# cape.net
KiCad netlist of a schematic drawn in Altium Designer
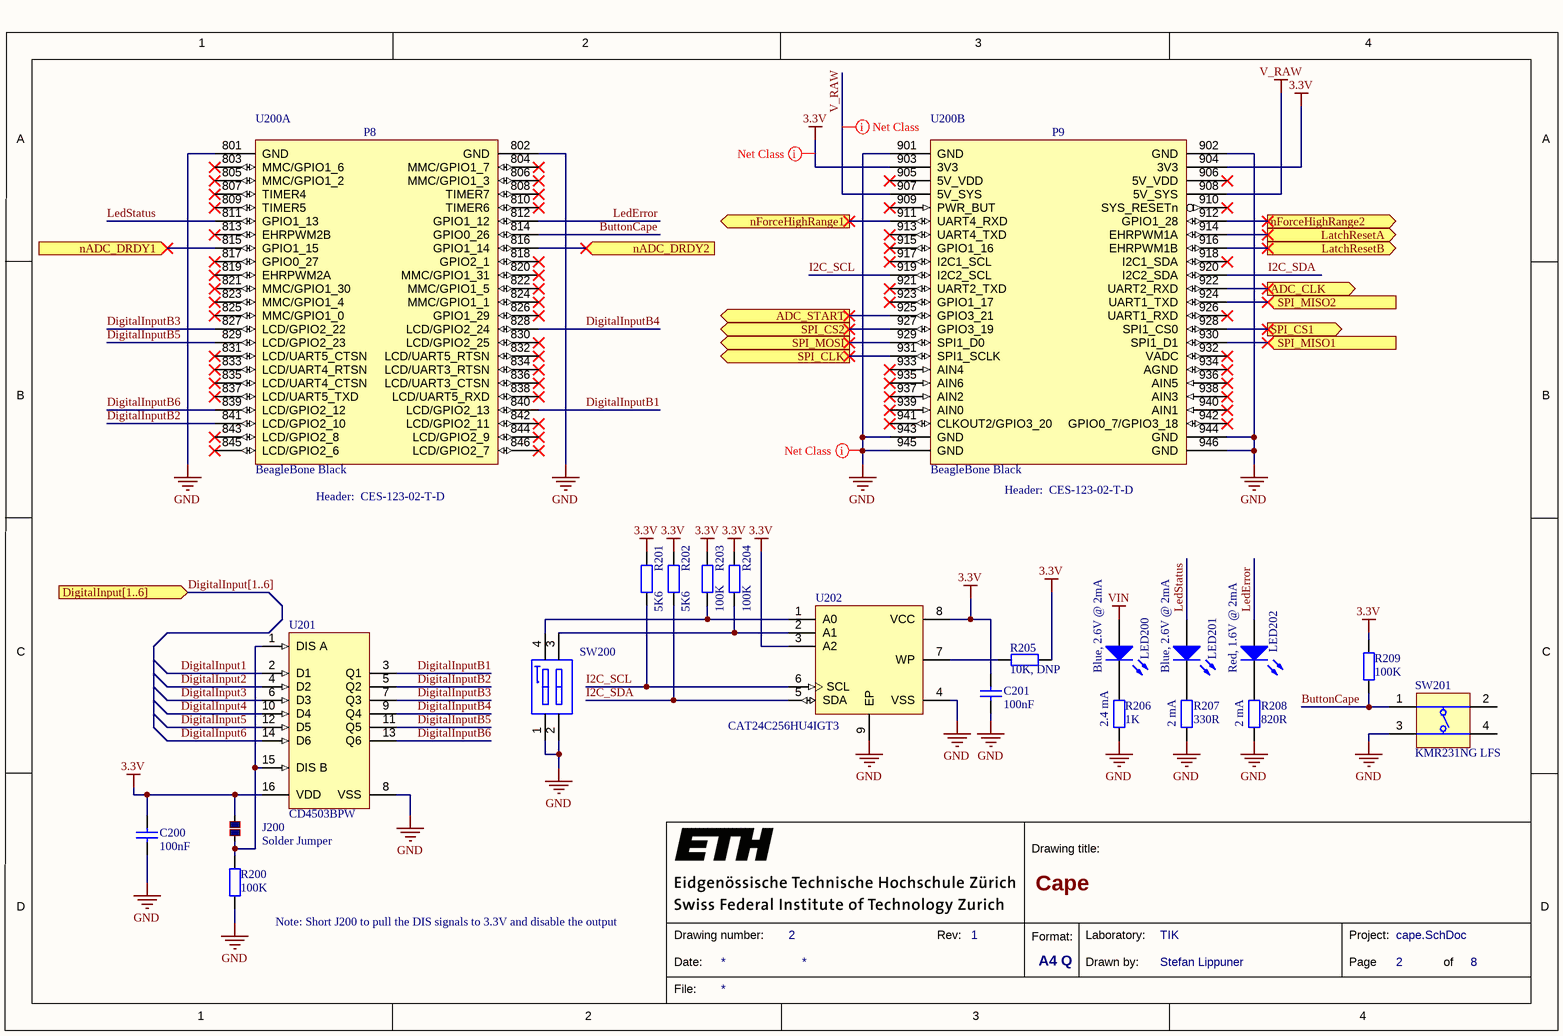
[diagram p0: cape.SchDoc]

(export (version "E")
  (design (tool "Eeschema 10.0.6"))
  (components
    (comp (ref "C200")
      (value "100nF")
      (footprint "CAPC0402(1005)60_L")
      (description "CAP 100nF 16V -20% to +80% 0402 (1005 Metric) Thickness 0.6mm SMD")
      (fields (field (name "TOLERANCE") "-20% to +80%"))
      (libsource (lib "Altium Content Vault") (part "CMP-1034-02071-1"))
    )
    (comp (ref "C201")
      (value "100nF")
      (footprint "CAPC0402(1005)60_L")
      (description "CAP 100nF 16V -20% to +80% 0402 (1005 Metric) Thickness 0.6mm SMD")
      (fields (field (name "TOLERANCE") "-20% to +80%"))
      (libsource (lib "Altium Content Vault") (part "CMP-1034-02071-1"))
    )
    (comp (ref "J200")
      (value "Solder Jumper")
      (footprint "Small Solder Jumper")
      (libsource (lib "ETHZ Vault") (part "CMP-00005-1"))
    )
    (comp (ref "LED200")
      (value "Blue, 2.6V @ 2mA")
      (footprint "0603_A")
      (description "SMD mono-color Chip LED, WL-SMCW, Blue")
      (fields (field (name "PARTNUMBER") "150060BS75000") (field (name "MANUFACTURER") "Wuerth Elektronik"))
      (libsource (lib "Altium Content Vault") (part "CMP-1426-00003-1"))
    )
    (comp (ref "LED201")
      (value "Blue, 2.6V @ 2mA")
      (footprint "0603_A")
      (description "SMD mono-color Chip LED, WL-SMCW, Blue")
      (fields (field (name "PARTNUMBER") "150060BS75000") (field (name "MANUFACTURER") "Wuerth Elektronik"))
      (libsource (lib "Altium Content Vault") (part "CMP-1426-00003-1"))
    )
    (comp (ref "LED202")
      (value "Red, 1.6V @ 2mA")
      (footprint "0603_A")
      (description "SMD mono-color Chip LED, WL-SMCW, Red")
      (fields (field (name "MANUFACTURER") "Wuerth Elektronik") (field (name "PARTNUMBER") "150060RS75000"))
      (libsource (lib "Altium Content Vault") (part "WE-LED_K1A2-2"))
    )
    (comp (ref "P8")
      (value "CES-123-02-T-D (BOM)")
      (libsource (lib "CES-123-02-T-D") (part "CES-123-02-T-D (BOM)"))
    )
    (comp (ref "P9")
      (value "CES-123-02-T-D (BOM)")
      (libsource (lib "CES-123-02-T-D") (part "CES-123-02-T-D (BOM)"))
    )
    (comp (ref "R200")
      (value "100K")
      (footprint "RESC0402(1005)_L")
      (description "100K 0.063W 1% 0402 (1005 Metric)  SMD")
      (fields (field (name "TOLERANCE") "1 %") (field (name "POWER") "0.063 W"))
      (libsource (lib "Altium Content Vault") (part "CMP-1011-00736"))
    )
    (comp (ref "R201")
      (value "5K6")
      (footprint "RESC0402(1005)_L")
      (description "5K6 0.063W 5% 0402 (1005 Metric)  SMD")
      (fields (field (name "TOLERANCE") "5 %") (field (name "POWER") "0.063 W"))
      (libsource (lib "Altium Content Vault") (part "CMP-1011-00092-1"))
    )
    (comp (ref "R202")
      (value "5K6")
      (footprint "RESC0402(1005)_L")
      (description "5K6 0.063W 5% 0402 (1005 Metric)  SMD")
      (fields (field (name "TOLERANCE") "5 %") (field (name "POWER") "0.063 W"))
      (libsource (lib "Altium Content Vault") (part "CMP-1011-00092-1"))
    )
    (comp (ref "R203")
      (value "100K")
      (footprint "RESC0402(1005)_L")
      (description "100K 0.063W 1% 0402 (1005 Metric)  SMD")
      (fields (field (name "POWER") "0.063 W") (field (name "TOLERANCE") "1 %"))
      (libsource (lib "Altium Content Vault") (part "CMP-1011-00736"))
    )
    (comp (ref "R204")
      (value "100K")
      (footprint "RESC0402(1005)_L")
      (description "100K 0.063W 1% 0402 (1005 Metric)  SMD")
      (fields (field (name "POWER") "0.063 W") (field (name "TOLERANCE") "1 %"))
      (libsource (lib "Altium Content Vault") (part "CMP-1011-00736"))
    )
    (comp (ref "R205")
      (value "10K, DNP")
      (footprint "RESC0402(1005)_L")
      (description "10K 0.063W 1% 0402 (1005 Metric)  SMD")
      (fields (field (name "TOLERANCE") "1 %") (field (name "POWER") "0.063 W"))
      (libsource (lib "Altium Content Vault") (part "CMP-1011-00623-1"))
    )
    (comp (ref "R206")
      (value "1K")
      (footprint "RESC0402(1005)_L")
      (description "1K 0.063W 1% 0402 (1005 Metric)  SMD")
      (fields (field (name "TOLERANCE") "1 %") (field (name "POWER") "0.063 W"))
      (libsource (lib "Altium Content Vault") (part "RES"))
    )
    (comp (ref "R207")
      (value "330R")
      (footprint "RESC0402(1005)_L")
      (description "330R 0.063W 5% 0402 (1005 Metric)  SMD")
      (fields (field (name "TOLERANCE") "5 %") (field (name "POWER") "0.063 W"))
      (libsource (lib "Altium Content Vault") (part "CMP-1011-00062-1"))
    )
    (comp (ref "R208")
      (value "820R")
      (footprint "RESC0402(1005)_L")
      (description "820R 0.063W 5% 0402 (1005 Metric)  SMD")
      (fields (field (name "TOLERANCE") "5 %") (field (name "POWER") "0.063 W"))
      (libsource (lib "Altium Content Vault") (part "CMP-1011-00072-1"))
    )
    (comp (ref "R209")
      (value "100K")
      (footprint "RESC0402(1005)_L")
      (description "100K 0.063W 1% 0402 (1005 Metric)  SMD")
      (fields (field (name "TOLERANCE") "1 %") (field (name "POWER") "0.063 W"))
      (libsource (lib "Altium Content Vault") (part "CMP-1011-00736"))
    )
    (comp (ref "SW200")
      (value "218-2LPST")
      (footprint "416131160802")
      (description "Switch DIP ON OFF SPST 2 Recessed Slide 0.025A 24VDC Gull Wing 1.27mm SMD")
      (fields (field (name "MANUFACTURER") "CTS Electrocomponents"))
      (libsource (lib "ETHZ Vault") (part "WE-DIP-SW-4"))
    )
    (comp (ref "SW201")
      (value "KMR231NG LFS")
      (footprint "KRM 2 Series")
      (description "SWITCH TACTILE SPST-NO 0.05A 32V")
      (fields (field (name "MANUFACTURER") "C&K Components"))
      (libsource (lib "ETHZ Vault") (part "SW-Push Button"))
    )
    (comp (ref "U200") (value "BeagleBone Black") (libsource (lib "ETHZ Vault") (part "CMP-00111-2")))
    (comp (ref "U201")
      (value "CD4503BPW")
      (footprint "PW0016A_L")
      (description "CMOS Hex Non-Inverting Buffer with 3-State Outputs, PW0016A, TUBE")
      (fields
        (field (name "MANUFACTURER") "Texas Instruments")
        (field (name "GENERIC PART NUMBER") "CD4503B")
      )
      (libsource (lib "Altium Content Vault") (part "TI-CD4503B-16"))
    )
    (comp (ref "U202")
      (value "CAT24C256HU4IGT3")
      (footprint "UDFN-MU8")
      (description "IC EEPROM 256KBIT 400KHZ 8UDFN")
      (fields (field (name "MANUFACTURER") "ON Semiconductor"))
      (libsource (lib "ETHZ Vault") (part "CAT24C256"))
    )
  )
  (nets
    (net (code "1") (name "/ADC_CLK") (class "Default")
      (node (ref "U200") (pin "922") (pinfunction "UART2_RXD_922") (pintype "bidirectional+no_connect"))
    )
    (net (code "2") (name "/ADC_START") (class "Default")
      (node (ref "U200") (pin "925") (pinfunction "GPIO3_21_925") (pintype "bidirectional+no_connect"))
    )
    (net (code "3") (name "/ButtonCape") (class "Default")
      (node (ref "R209") (pin "1") (pinfunction "1_1") (pintype "passive"))
      (node (ref "SW201") (pin "1") (pinfunction "T1_1") (pintype "passive"))
      (node (ref "U200") (pin "814") (pinfunction "GPIO0_26_814") (pintype "bidirectional"))
    )
    (net (code "4") (name "/DigitalInput1") (class "Default")
      (node (ref "U201") (pin "2") (pinfunction "D1_2") (pintype "input"))
    )
    (net (code "5") (name "/DigitalInput2") (class "Default")
      (node (ref "U201") (pin "4") (pinfunction "D2_4") (pintype "input"))
    )
    (net (code "6") (name "/DigitalInput3") (class "Default")
      (node (ref "U201") (pin "6") (pinfunction "D3_6") (pintype "input"))
    )
    (net (code "7") (name "/DigitalInput4") (class "Default")
      (node (ref "U201") (pin "10") (pinfunction "D4_10") (pintype "input"))
    )
    (net (code "8") (name "/DigitalInput5") (class "Default")
      (node (ref "U201") (pin "12") (pinfunction "D5_12") (pintype "input"))
    )
    (net (code "9") (name "/DigitalInput6") (class "Default")
      (node (ref "U201") (pin "14") (pinfunction "D6_14") (pintype "input"))
    )
    (net (code "10") (name "/DigitalInputB1") (class "Default")
      (node (ref "U200") (pin "840") (pinfunction "LCD/GPIO2_13_840") (pintype "bidirectional"))
      (node (ref "U201") (pin "3") (pinfunction "Q1_3") (pintype "tri_state"))
    )
    (net (code "11") (name "/DigitalInputB2") (class "Default")
      (node (ref "U200") (pin "841") (pinfunction "LCD/GPIO2_10_841") (pintype "bidirectional"))
      (node (ref "U201") (pin "5") (pinfunction "Q2_5") (pintype "tri_state"))
    )
    (net (code "12") (name "/DigitalInputB3") (class "Default")
      (node (ref "U200") (pin "827") (pinfunction "LCD/GPIO2_22_827") (pintype "bidirectional"))
      (node (ref "U201") (pin "7") (pinfunction "Q3_7") (pintype "tri_state"))
    )
    (net (code "13") (name "/DigitalInputB4") (class "Default")
      (node (ref "U200") (pin "828") (pinfunction "LCD/GPIO2_24_828") (pintype "bidirectional"))
      (node (ref "U201") (pin "9") (pinfunction "Q4_9") (pintype "tri_state"))
    )
    (net (code "14") (name "/DigitalInputB5") (class "Default")
      (node (ref "U200") (pin "829") (pinfunction "LCD/GPIO2_23_829") (pintype "bidirectional"))
      (node (ref "U201") (pin "11") (pinfunction "Q5_11") (pintype "tri_state"))
    )
    (net (code "15") (name "/DigitalInputB6") (class "Default")
      (node (ref "U200") (pin "839") (pinfunction "LCD/GPIO2_12_839") (pintype "bidirectional"))
      (node (ref "U201") (pin "13") (pinfunction "Q6_13") (pintype "tri_state"))
    )
    (net (code "17") (name "/I2C_SCL") (class "Default")
      (node (ref "R201") (pin "1") (pinfunction "1_1") (pintype "passive"))
      (node (ref "U200") (pin "919") (pinfunction "I2C2_SCL_919") (pintype "bidirectional"))
      (node (ref "U202") (pin "6") (pinfunction "SCL_6") (pintype "input"))
    )
    (net (code "18") (name "/I2C_SDA") (class "Default")
      (node (ref "R202") (pin "1") (pinfunction "1_1") (pintype "passive"))
      (node (ref "U200") (pin "920") (pinfunction "I2C2_SDA_920") (pintype "bidirectional"))
      (node (ref "U202") (pin "5") (pinfunction "SDA_5") (pintype "bidirectional"))
    )
    (net (code "19") (name "/LatchResetA") (class "Default")
      (node (ref "U200") (pin "914") (pinfunction "EHRPWM1A_914") (pintype "bidirectional+no_connect"))
    )
    (net (code "20") (name "/LatchResetB") (class "Default")
      (node (ref "U200") (pin "916") (pinfunction "EHRPWM1B_916") (pintype "bidirectional+no_connect"))
    )
    (net (code "21") (name "/LedError") (class "Default")
      (node (ref "LED202") (pin "2") (pinfunction "A_2") (pintype "passive"))
      (node (ref "U200") (pin "812") (pinfunction "GPIO1_12_812") (pintype "bidirectional"))
    )
    (net (code "22") (name "/LedStatus") (class "Default")
      (node (ref "LED201") (pin "2") (pinfunction "A_2") (pintype "passive"))
      (node (ref "U200") (pin "811") (pinfunction "GPIO1_13_811") (pintype "bidirectional"))
    )
    (net (code "23") (name "/SPI_CLK") (class "Default")
      (node (ref "U200") (pin "931") (pinfunction "SPI1_SCLK_931") (pintype "bidirectional+no_connect"))
    )
    (net (code "24") (name "/SPI_CS1") (class "Default")
      (node (ref "U200") (pin "928") (pinfunction "SPI1_CS0_928") (pintype "bidirectional+no_connect"))
    )
    (net (code "25") (name "/SPI_CS2") (class "Default")
      (node (ref "U200") (pin "927") (pinfunction "GPIO3_19_927") (pintype "bidirectional+no_connect"))
    )
    (net (code "26") (name "/SPI_MISO1") (class "Default")
      (node (ref "U200") (pin "930") (pinfunction "SPI1_D1_930") (pintype "bidirectional+no_connect"))
    )
    (net (code "27") (name "/SPI_MISO2") (class "Default")
      (node (ref "U200") (pin "924") (pinfunction "UART1_TXD_924") (pintype "bidirectional+no_connect"))
    )
    (net (code "28") (name "/SPI_MOSI") (class "Default")
      (node (ref "U200") (pin "929") (pinfunction "SPI1_D0_929") (pintype "bidirectional+no_connect"))
    )
    (net (code "29") (name "/nADC_DRDY1") (class "Default")
      (node (ref "U200") (pin "815") (pinfunction "GPIO1_15_815") (pintype "bidirectional+no_connect"))
    )
    (net (code "30") (name "/nADC_DRDY2") (class "Default")
      (node (ref "U200") (pin "816") (pinfunction "GPIO1_14_816") (pintype "bidirectional+no_connect"))
    )
    (net (code "31") (name "/nForceHighRange1") (class "Default")
      (node (ref "U200") (pin "911") (pinfunction "UART4_RXD_911") (pintype "bidirectional+no_connect"))
    )
    (net (code "32") (name "/nForceHighRange2") (class "Default")
      (node (ref "U200") (pin "912") (pinfunction "GPIO1_28_912") (pintype "bidirectional+no_connect"))
    )
    (net (code "33") (name "3.3V") (class "Default")
      (node (ref "C200") (pin "2") (pinfunction "2_2") (pintype "passive"))
      (node (ref "C201") (pin "2") (pinfunction "2_2") (pintype "passive"))
      (node (ref "J200") (pin "2") (pintype "passive"))
      (node (ref "R201") (pin "2") (pinfunction "2_2") (pintype "passive"))
      (node (ref "R202") (pin "2") (pinfunction "2_2") (pintype "passive"))
      (node (ref "R203") (pin "2") (pinfunction "2_2") (pintype "passive"))
      (node (ref "R204") (pin "2") (pinfunction "2_2") (pintype "passive"))
      (node (ref "R205") (pin "2") (pinfunction "2_2") (pintype "passive"))
      (node (ref "R209") (pin "2") (pinfunction "2_2") (pintype "passive"))
      (node (ref "U200") (pin "903") (pinfunction "3V3_903") (pintype "power_in"))
      (node (ref "U200") (pin "904") (pinfunction "3V3_904") (pintype "power_in"))
      (node (ref "U201") (pin "16") (pinfunction "VDD_16") (pintype "power_in"))
      (node (ref "U202") (pin "3") (pinfunction "A2_3") (pintype "passive"))
      (node (ref "U202") (pin "8") (pinfunction "VCC_8") (pintype "power_in"))
    )
    (net (code "34") (name "GND") (class "Default")
      (node (ref "C200") (pin "1") (pinfunction "1_1") (pintype "passive"))
      (node (ref "C201") (pin "1") (pinfunction "1_1") (pintype "passive"))
      (node (ref "R200") (pin "1") (pinfunction "1_1") (pintype "passive"))
      (node (ref "R206") (pin "1") (pinfunction "1_1") (pintype "passive"))
      (node (ref "R207") (pin "1") (pinfunction "1_1") (pintype "passive"))
      (node (ref "R208") (pin "1") (pinfunction "1_1") (pintype "passive"))
      (node (ref "SW200") (pin "1") (pinfunction "1_1") (pintype "passive"))
      (node (ref "SW200") (pin "2") (pinfunction "2_2") (pintype "passive"))
      (node (ref "SW201") (pin "3") (pinfunction "T3_3") (pintype "passive"))
      (node (ref "U200") (pin "801") (pinfunction "GND_801") (pintype "power_in"))
      (node (ref "U200") (pin "802") (pinfunction "GND_802") (pintype "power_in"))
      (node (ref "U200") (pin "901") (pinfunction "GND_901") (pintype "passive"))
      (node (ref "U200") (pin "902") (pinfunction "GND_902") (pintype "passive"))
      (node (ref "U200") (pin "943") (pinfunction "GND_943") (pintype "power_in"))
      (node (ref "U200") (pin "944") (pinfunction "GND_944") (pintype "power_in"))
      (node (ref "U200") (pin "945") (pinfunction "GND_945") (pintype "power_in"))
      (node (ref "U200") (pin "946") (pinfunction "GND_946") (pintype "power_in"))
      (node (ref "U201") (pin "8") (pinfunction "VSS_8") (pintype "power_in"))
      (node (ref "U202") (pin "4") (pinfunction "VSS_4") (pintype "power_in"))
      (node (ref "U202") (pin "9") (pinfunction "EP_9") (pintype "power_in"))
    )
    (net (code "35") (name "Net-(LED200-K)") (class "Default")
      (node (ref "LED200") (pin "1") (pinfunction "K_1") (pintype "passive"))
      (node (ref "R206") (pin "2") (pinfunction "2_2") (pintype "passive"))
    )
    (net (code "36") (name "Net-(LED201-K)") (class "Default")
      (node (ref "LED201") (pin "1") (pinfunction "K_1") (pintype "passive"))
      (node (ref "R207") (pin "2") (pinfunction "2_2") (pintype "passive"))
    )
    (net (code "37") (name "Net-(LED202-K)") (class "Default")
      (node (ref "LED202") (pin "1") (pinfunction "K_1") (pintype "passive"))
      (node (ref "R208") (pin "2") (pinfunction "2_2") (pintype "passive"))
    )
    (net (code "38") (name "Net-(U201-DIS_A)") (class "Default")
      (node (ref "J200") (pin "1") (pintype "passive"))
      (node (ref "R200") (pin "2") (pinfunction "2_2") (pintype "passive"))
      (node (ref "U201") (pin "1") (pinfunction "DIS_A_1") (pintype "input"))
      (node (ref "U201") (pin "15") (pinfunction "DIS_B_15") (pintype "input"))
    )
    (net (code "39") (name "Net-(U202-A0)") (class "Default")
      (node (ref "R203") (pin "1") (pinfunction "1_1") (pintype "passive"))
      (node (ref "SW200") (pin "4") (pinfunction "4_4") (pintype "passive"))
      (node (ref "U202") (pin "1") (pinfunction "A0_1") (pintype "passive"))
    )
    (net (code "40") (name "Net-(U202-A1)") (class "Default")
      (node (ref "R204") (pin "1") (pinfunction "1_1") (pintype "passive"))
      (node (ref "SW200") (pin "3") (pinfunction "3_3") (pintype "passive"))
      (node (ref "U202") (pin "2") (pinfunction "A1_2") (pintype "passive"))
    )
    (net (code "41") (name "Net-(U202-WP)") (class "Default")
      (node (ref "R205") (pin "1") (pinfunction "1_1") (pintype "passive"))
      (node (ref "U202") (pin "7") (pinfunction "WP_7") (pintype "passive"))
    )
    (net (code "42") (name "VIN") (class "Default")
      (node (ref "LED200") (pin "2") (pinfunction "A_2") (pintype "passive"))
    )
    (net (code "43") (name "V_RAW") (class "Default")
      (node (ref "U200") (pin "907") (pinfunction "5V_SYS_907") (pintype "power_in"))
      (node (ref "U200") (pin "908") (pinfunction "5V_SYS_908") (pintype "power_in"))
    )
    (net (code "44") (name "unconnected-(SW201-T2-Pad2)") (class "Default")
      (node (ref "SW201") (pin "2") (pinfunction "T2_2") (pintype "passive"))
    )
    (net (code "45") (name "unconnected-(SW201-T3-Pad4)") (class "Default")
      (node (ref "SW201") (pin "4") (pinfunction "T3_4") (pintype "passive"))
    )
    (net (code "46") (name "unconnected-(U200A-EHRPWM2A-Pad819)") (class "Default")
      (node (ref "U200") (pin "819") (pinfunction "EHRPWM2A_819") (pintype "bidirectional+no_connect"))
    )
    (net (code "47") (name "unconnected-(U200A-EHRPWM2B-Pad813)") (class "Default")
      (node (ref "U200") (pin "813") (pinfunction "EHRPWM2B_813") (pintype "bidirectional+no_connect"))
    )
    (net (code "48") (name "unconnected-(U200A-GPIO0_27-Pad817)") (class "Default")
      (node (ref "U200") (pin "817") (pinfunction "GPIO0_27_817") (pintype "bidirectional+no_connect"))
    )
    (net (code "49") (name "unconnected-(U200A-GPIO1_29-Pad826)") (class "Default")
      (node (ref "U200") (pin "826") (pinfunction "GPIO1_29_826") (pintype "bidirectional+no_connect"))
    )
    (net (code "50") (name "unconnected-(U200A-GPIO2_1-Pad818)") (class "Default")
      (node (ref "U200") (pin "818") (pinfunction "GPIO2_1_818") (pintype "bidirectional+no_connect"))
    )
    (net (code "51") (name "unconnected-(U200A-LCD{slash}GPIO2_6-Pad845)") (class "Default")
      (node (ref "U200") (pin "845") (pinfunction "LCD/GPIO2_6_845") (pintype "bidirectional+no_connect"))
    )
    (net (code "52") (name "unconnected-(U200A-LCD{slash}GPIO2_7-Pad846)") (class "Default")
      (node (ref "U200") (pin "846") (pinfunction "LCD/GPIO2_7_846") (pintype "bidirectional+no_connect"))
    )
    (net (code "53") (name "unconnected-(U200A-LCD{slash}GPIO2_8-Pad843)") (class "Default")
      (node (ref "U200") (pin "843") (pinfunction "LCD/GPIO2_8_843") (pintype "bidirectional+no_connect"))
    )
    (net (code "54") (name "unconnected-(U200A-LCD{slash}GPIO2_9-Pad844)") (class "Default")
      (node (ref "U200") (pin "844") (pinfunction "LCD/GPIO2_9_844") (pintype "bidirectional+no_connect"))
    )
    (net (code "55") (name "unconnected-(U200A-LCD{slash}GPIO2_11-Pad842)") (class "Default")
      (node (ref "U200") (pin "842") (pinfunction "LCD/GPIO2_11_842") (pintype "bidirectional+no_connect"))
    )
    (net (code "56") (name "unconnected-(U200A-LCD{slash}GPIO2_25-Pad830)") (class "Default")
      (node (ref "U200") (pin "830") (pinfunction "LCD/GPIO2_25_830") (pintype "bidirectional+no_connect"))
    )
    (net (code "57") (name "unconnected-(U200A-LCD{slash}UART3_CTSN-Pad836)") (class "Default")
      (node (ref "U200") (pin "836") (pinfunction "LCD/UART3_CTSN_836") (pintype "bidirectional+no_connect"))
    )
    (net (code "58") (name "unconnected-(U200A-LCD{slash}UART3_RTSN-Pad834)") (class "Default")
      (node (ref "U200") (pin "834") (pinfunction "LCD/UART3_RTSN_834") (pintype "bidirectional+no_connect"))
    )
    (net (code "59") (name "unconnected-(U200A-LCD{slash}UART4_CTSN-Pad835)") (class "Default")
      (node (ref "U200") (pin "835") (pinfunction "LCD/UART4_CTSN_835") (pintype "bidirectional+no_connect"))
    )
    (net (code "60") (name "unconnected-(U200A-LCD{slash}UART4_RTSN-Pad833)") (class "Default")
      (node (ref "U200") (pin "833") (pinfunction "LCD/UART4_RTSN_833") (pintype "bidirectional+no_connect"))
    )
    (net (code "61") (name "unconnected-(U200A-LCD{slash}UART5_CTSN-Pad831)") (class "Default")
      (node (ref "U200") (pin "831") (pinfunction "LCD/UART5_CTSN_831") (pintype "bidirectional+no_connect"))
    )
    (net (code "62") (name "unconnected-(U200A-LCD{slash}UART5_RTSN-Pad832)") (class "Default")
      (node (ref "U200") (pin "832") (pinfunction "LCD/UART5_RTSN_832") (pintype "bidirectional+no_connect"))
    )
    (net (code "63") (name "unconnected-(U200A-LCD{slash}UART5_RXD-Pad838)") (class "Default")
      (node (ref "U200") (pin "838") (pinfunction "LCD/UART5_RXD_838") (pintype "bidirectional+no_connect"))
    )
    (net (code "64") (name "unconnected-(U200A-LCD{slash}UART5_TXD-Pad837)") (class "Default")
      (node (ref "U200") (pin "837") (pinfunction "LCD/UART5_TXD_837") (pintype "bidirectional+no_connect"))
    )
    (net (code "65") (name "unconnected-(U200A-MMC{slash}GPIO1_0-Pad825)") (class "Default")
      (node (ref "U200") (pin "825") (pinfunction "MMC/GPIO1_0_825") (pintype "bidirectional+no_connect"))
    )
    (net (code "66") (name "unconnected-(U200A-MMC{slash}GPIO1_1-Pad824)") (class "Default")
      (node (ref "U200") (pin "824") (pinfunction "MMC/GPIO1_1_824") (pintype "bidirectional+no_connect"))
    )
    (net (code "67") (name "unconnected-(U200A-MMC{slash}GPIO1_2-Pad805)") (class "Default")
      (node (ref "U200") (pin "805") (pinfunction "MMC/GPIO1_2_805") (pintype "bidirectional+no_connect"))
    )
    (net (code "68") (name "unconnected-(U200A-MMC{slash}GPIO1_3-Pad806)") (class "Default")
      (node (ref "U200") (pin "806") (pinfunction "MMC/GPIO1_3_806") (pintype "bidirectional+no_connect"))
    )
    (net (code "69") (name "unconnected-(U200A-MMC{slash}GPIO1_4-Pad823)") (class "Default")
      (node (ref "U200") (pin "823") (pinfunction "MMC/GPIO1_4_823") (pintype "bidirectional+no_connect"))
    )
    (net (code "70") (name "unconnected-(U200A-MMC{slash}GPIO1_5-Pad822)") (class "Default")
      (node (ref "U200") (pin "822") (pinfunction "MMC/GPIO1_5_822") (pintype "bidirectional+no_connect"))
    )
    (net (code "71") (name "unconnected-(U200A-MMC{slash}GPIO1_6-Pad803)") (class "Default")
      (node (ref "U200") (pin "803") (pinfunction "MMC/GPIO1_6_803") (pintype "bidirectional+no_connect"))
    )
    (net (code "72") (name "unconnected-(U200A-MMC{slash}GPIO1_7-Pad804)") (class "Default")
      (node (ref "U200") (pin "804") (pinfunction "MMC/GPIO1_7_804") (pintype "bidirectional+no_connect"))
    )
    (net (code "73") (name "unconnected-(U200A-MMC{slash}GPIO1_30-Pad821)") (class "Default")
      (node (ref "U200") (pin "821") (pinfunction "MMC/GPIO1_30_821") (pintype "bidirectional+no_connect"))
    )
    (net (code "74") (name "unconnected-(U200A-MMC{slash}GPIO1_31-Pad820)") (class "Default")
      (node (ref "U200") (pin "820") (pinfunction "MMC/GPIO1_31_820") (pintype "bidirectional+no_connect"))
    )
    (net (code "75") (name "unconnected-(U200A-TIMER4-Pad807)") (class "Default")
      (node (ref "U200") (pin "807") (pinfunction "TIMER4_807") (pintype "bidirectional+no_connect"))
    )
    (net (code "76") (name "unconnected-(U200A-TIMER5-Pad809)") (class "Default")
      (node (ref "U200") (pin "809") (pinfunction "TIMER5_809") (pintype "bidirectional+no_connect"))
    )
    (net (code "77") (name "unconnected-(U200A-TIMER6-Pad810)") (class "Default")
      (node (ref "U200") (pin "810") (pinfunction "TIMER6_810") (pintype "bidirectional+no_connect"))
    )
    (net (code "78") (name "unconnected-(U200A-TIMER7-Pad808)") (class "Default")
      (node (ref "U200") (pin "808") (pinfunction "TIMER7_808") (pintype "bidirectional+no_connect"))
    )
    (net (code "79") (name "unconnected-(U200B-5V_VDD-Pad905)") (class "Default")
      (node (ref "U200") (pin "905") (pinfunction "5V_VDD_905") (pintype "power_in+no_connect"))
    )
    (net (code "80") (name "unconnected-(U200B-5V_VDD-Pad906)") (class "Default")
      (node (ref "U200") (pin "906") (pinfunction "5V_VDD_906") (pintype "power_in+no_connect"))
    )
    (net (code "81") (name "unconnected-(U200B-AGND-Pad934)") (class "Default")
      (node (ref "U200") (pin "934") (pinfunction "AGND_934") (pintype "bidirectional+no_connect"))
    )
    (net (code "82") (name "unconnected-(U200B-AIN0-Pad939)") (class "Default")
      (node (ref "U200") (pin "939") (pinfunction "AIN0_939") (pintype "input+no_connect"))
    )
    (net (code "83") (name "unconnected-(U200B-AIN1-Pad940)") (class "Default")
      (node (ref "U200") (pin "940") (pinfunction "AIN1_940") (pintype "input+no_connect"))
    )
    (net (code "84") (name "unconnected-(U200B-AIN2-Pad937)") (class "Default")
      (node (ref "U200") (pin "937") (pinfunction "AIN2_937") (pintype "input+no_connect"))
    )
    (net (code "85") (name "unconnected-(U200B-AIN3-Pad938)") (class "Default")
      (node (ref "U200") (pin "938") (pinfunction "AIN3_938") (pintype "input+no_connect"))
    )
    (net (code "86") (name "unconnected-(U200B-AIN4-Pad933)") (class "Default")
      (node (ref "U200") (pin "933") (pinfunction "AIN4_933") (pintype "input+no_connect"))
    )
    (net (code "87") (name "unconnected-(U200B-AIN5-Pad936)") (class "Default")
      (node (ref "U200") (pin "936") (pinfunction "AIN5_936") (pintype "input+no_connect"))
    )
    (net (code "88") (name "unconnected-(U200B-AIN6-Pad935)") (class "Default")
      (node (ref "U200") (pin "935") (pinfunction "AIN6_935") (pintype "input+no_connect"))
    )
    (net (code "89") (name "unconnected-(U200B-CLKOUT2{slash}GPIO3_20-Pad941)") (class "Default")
      (node (ref "U200") (pin "941") (pinfunction "CLKOUT2/GPIO3_20_941") (pintype "bidirectional+no_connect"))
    )
    (net (code "90") (name "unconnected-(U200B-GPIO0_7{slash}GPIO3_18-Pad942)") (class "Default")
      (node (ref "U200") (pin "942") (pinfunction "GPIO0_7/GPIO3_18_942") (pintype "bidirectional+no_connect"))
    )
    (net (code "91") (name "unconnected-(U200B-GPIO1_16-Pad915)") (class "Default")
      (node (ref "U200") (pin "915") (pinfunction "GPIO1_16_915") (pintype "bidirectional+no_connect"))
    )
    (net (code "92") (name "unconnected-(U200B-GPIO1_17-Pad923)") (class "Default")
      (node (ref "U200") (pin "923") (pinfunction "GPIO1_17_923") (pintype "bidirectional+no_connect"))
    )
    (net (code "93") (name "unconnected-(U200B-I2C1_SCL-Pad917)") (class "Default")
      (node (ref "U200") (pin "917") (pinfunction "I2C1_SCL_917") (pintype "bidirectional+no_connect"))
    )
    (net (code "94") (name "unconnected-(U200B-I2C1_SDA-Pad918)") (class "Default")
      (node (ref "U200") (pin "918") (pinfunction "I2C1_SDA_918") (pintype "bidirectional+no_connect"))
    )
    (net (code "95") (name "unconnected-(U200B-PWR_BUT-Pad909)") (class "Default")
      (node (ref "U200") (pin "909") (pinfunction "PWR_BUT_909") (pintype "input+no_connect"))
    )
    (net (code "96") (name "unconnected-(U200B-SYS_RESETn-Pad910)") (class "Default")
      (node (ref "U200") (pin "910") (pinfunction "SYS_RESETn_910") (pintype "output+no_connect"))
    )
    (net (code "97") (name "unconnected-(U200B-UART1_RXD-Pad926)") (class "Default")
      (node (ref "U200") (pin "926") (pinfunction "UART1_RXD_926") (pintype "bidirectional+no_connect"))
    )
    (net (code "98") (name "unconnected-(U200B-UART2_TXD-Pad921)") (class "Default")
      (node (ref "U200") (pin "921") (pinfunction "UART2_TXD_921") (pintype "bidirectional+no_connect"))
    )
    (net (code "99") (name "unconnected-(U200B-UART4_TXD-Pad913)") (class "Default")
      (node (ref "U200") (pin "913") (pinfunction "UART4_TXD_913") (pintype "bidirectional+no_connect"))
    )
    (net (code "100") (name "unconnected-(U200B-VADC-Pad932)") (class "Default")
      (node (ref "U200") (pin "932") (pinfunction "VADC_932") (pintype "bidirectional+no_connect"))
    )
  )
)
